# batteryholder2S6P_vertical_top_2.net
KiCad netlist of a schematic drawn in EAGLE
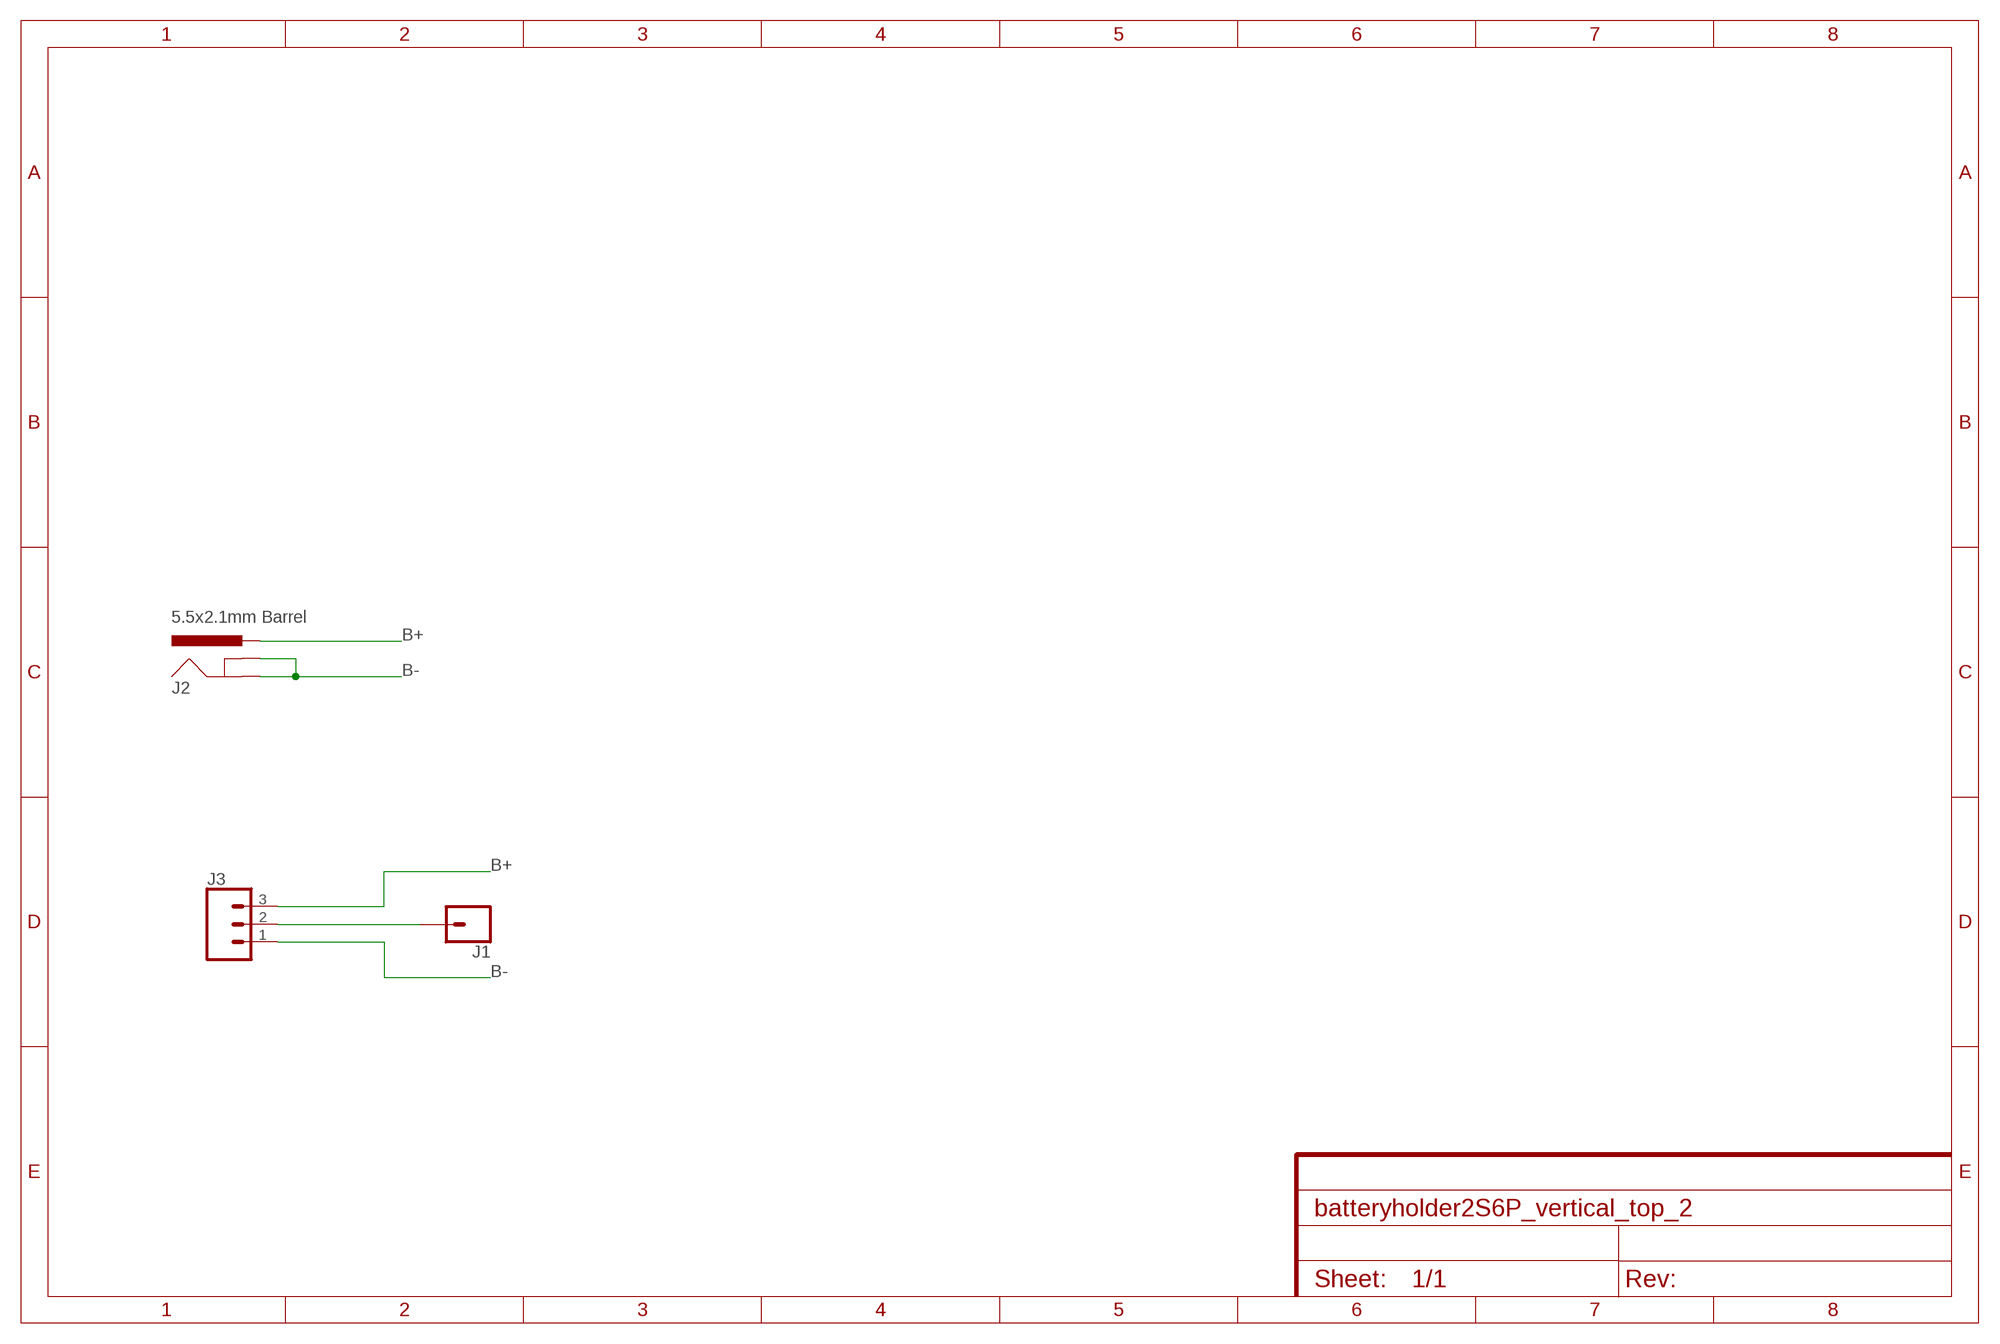
[diagram p0: schematic, sheet 1]

(export (version "E")
  (design (tool "Eeschema 10.0.6"))
  (components
    (comp (ref "J1")
      (value "CONN_01PTH_2MM")
      (footprint "eagle-import:1X01_2MM")
      (libsource (lib "eagle-import") (part "CONN_01PTH_2MM"))
    )
    (comp (ref "J2")
      (value "5.5x2.1mm Barrel")
      (footprint "eagle-import:POWER_JACK_SMD")
      (libsource (lib "eagle-import") (part "POWER_JACKSMD"))
    )
    (comp (ref "J3")
      (value "CONN_03-SCREW-5MM")
      (footprint "eagle-import:SCREWTERMINAL-5MM-3")
      (libsource (lib "eagle-import") (part "CONN_03-SCREW-5MM"))
    )
  )
  (nets
    (net (code "1") (name "/B+") (class "Default")
      (node (ref "J2") (pin "VIN0") (pinfunction "PWR_VIN0") (pintype "bidirectional"))
      (node (ref "J3") (pin "3") (pinfunction "3_3") (pintype "passive"))
    )
    (net (code "2") (name "/B-") (class "Default")
      (node (ref "J2") (pin "GND") (pinfunction "GNDBREAK_GND") (pintype "bidirectional"))
      (node (ref "J2") (pin "P$4") (pinfunction "GND_P$4") (pintype "bidirectional"))
      (node (ref "J3") (pin "1") (pinfunction "1_1") (pintype "passive"))
    )
    (net (code "3") (name "Net-(J1-Pad1)") (class "Default")
      (node (ref "J1") (pin "1") (pinfunction "1_1") (pintype "passive"))
      (node (ref "J3") (pin "2") (pinfunction "2_2") (pintype "passive"))
    )
  )
)
